# Programming_interface.net
KiCad netlist of a schematic drawn in Altium Designer
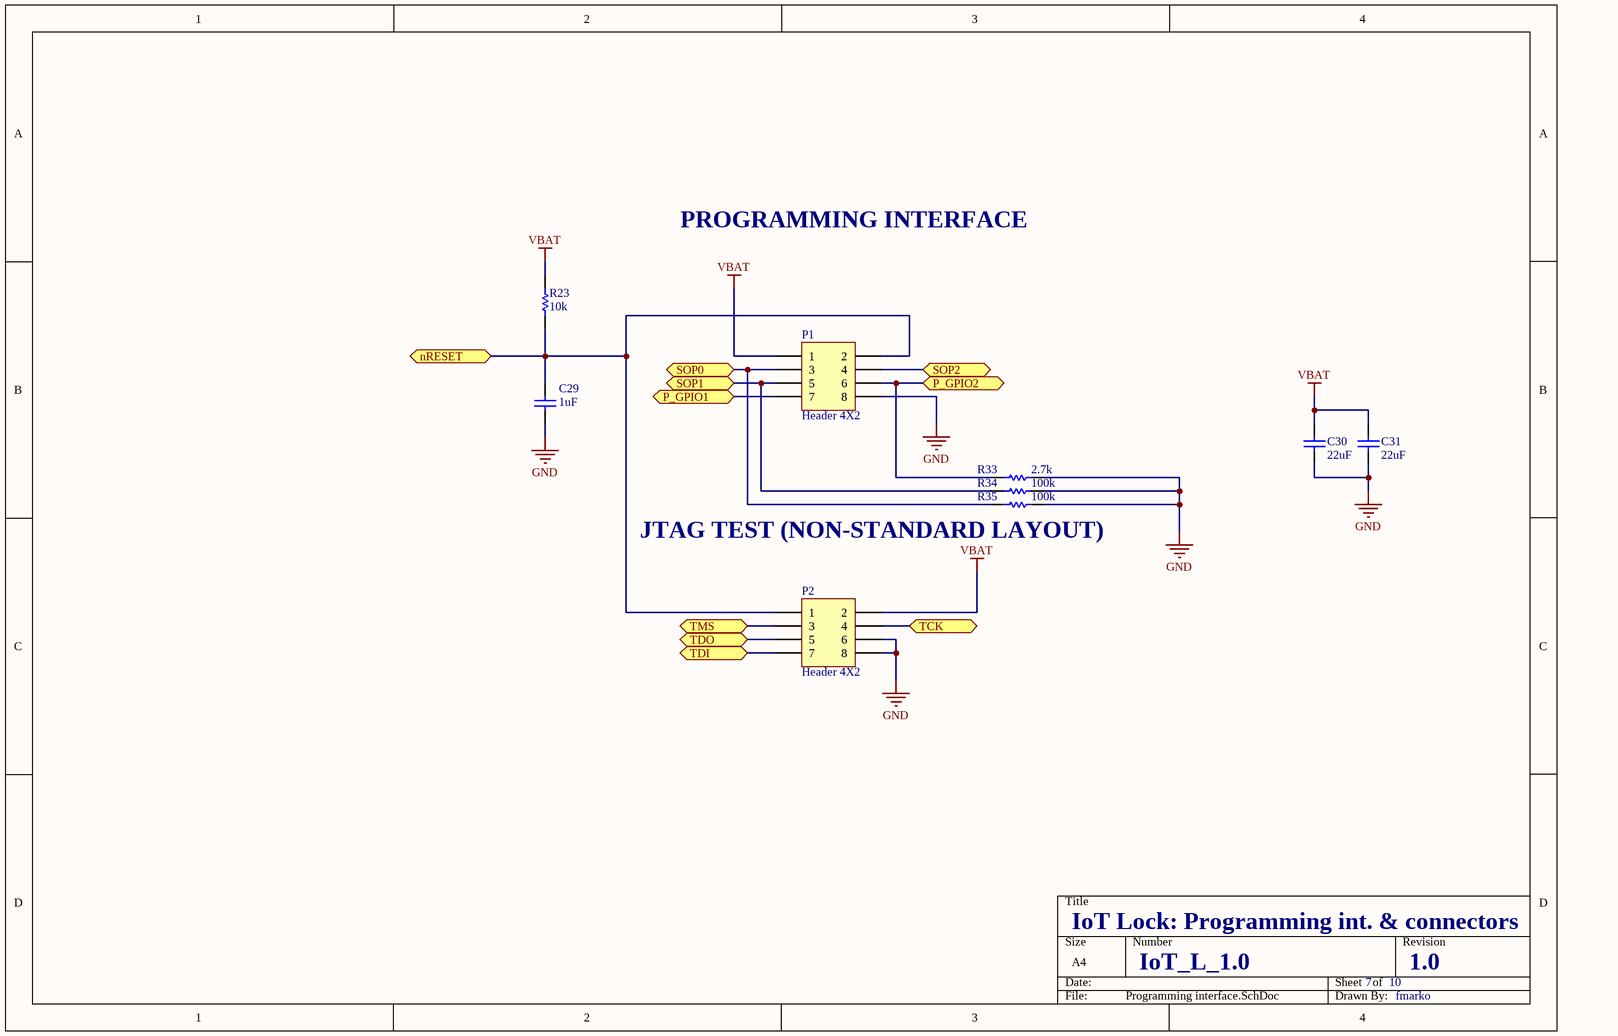
[diagram p0: Programming interface.SchDoc]

(export (version "E")
  (design (tool "Eeschema 10.0.6"))
  (components
    (comp (ref "C29")
      (value "1uF")
      (footprint "0402")
      (description "Capacitor")
      (fields (field (name "Comment") "GRM1555C1HR50BA01D") (field (name "PUBLISHER") "Altium Limited"))
      (libsource (lib "Miscellaneous Devices") (part "Cap"))
    )
    (comp (ref "C30")
      (value "22uF")
      (footprint "1608[0603]")
      (description "Capacitor")
      (fields (field (name "Comment") "GRM1555C1HR50BA01D") (field (name "PUBLISHER") "Altium Limited"))
      (libsource (lib "Miscellaneous Devices") (part "Cap"))
    )
    (comp (ref "C31")
      (value "22uF")
      (footprint "1608[0603]")
      (description "Capacitor")
      (fields (field (name "Comment") "GRM1555C1HR50BA01D") (field (name "PUBLISHER") "Altium Limited"))
      (libsource (lib "Miscellaneous Devices") (part "Cap"))
    )
    (comp (ref "P1")
      (value "Header 4X2")
      (footprint "HDR2X4")
      (description "Header, 4-Pin, Dual row")
      (fields (field (name "PUBLISHER") "Altium Limited"))
      (libsource (lib "Miscellaneous Connectors") (part "Header 4X2"))
    )
    (comp (ref "P2")
      (value "Header 4X2")
      (footprint "HDR2X4")
      (description "Header, 4-Pin, Dual row")
      (fields (field (name "PUBLISHER") "Altium Limited"))
      (libsource (lib "Miscellaneous Connectors") (part "Header 4X2"))
    )
    (comp (ref "R23")
      (value "10k")
      (footprint "0402")
      (description "Semiconductor Resistor")
      (fields (field (name "Comment") "Res Semi") (field (name "PUBLISHER") "Altium Limited"))
      (libsource (lib "Miscellaneous Devices") (part "Res Semi"))
    )
    (comp (ref "R33")
      (value "2.7k")
      (footprint "0402")
      (description "Semiconductor Resistor")
      (fields (field (name "Comment") "Res Semi") (field (name "PUBLISHER") "Altium Limited"))
      (libsource (lib "Miscellaneous Devices") (part "Res Semi"))
    )
    (comp (ref "R34")
      (value "100k")
      (footprint "0402")
      (description "Semiconductor Resistor")
      (fields (field (name "Comment") "Res Semi") (field (name "PUBLISHER") "Altium Limited"))
      (libsource (lib "Miscellaneous Devices") (part "Res Semi"))
    )
    (comp (ref "R35")
      (value "100k")
      (footprint "0402")
      (description "Semiconductor Resistor")
      (fields (field (name "Comment") "Res Semi") (field (name "PUBLISHER") "Altium Limited"))
      (libsource (lib "Miscellaneous Devices") (part "Res Semi"))
    )
  )
  (nets
    (net (code "1") (name "/P_GPIO1") (class "Default")
      (node (ref "P1") (pin "7") (pinfunction "7_7") (pintype "passive"))
    )
    (net (code "2") (name "/P_GPIO2") (class "Default")
      (node (ref "P1") (pin "6") (pinfunction "6_6") (pintype "passive"))
      (node (ref "R33") (pin "2") (pinfunction "2_2") (pintype "passive"))
    )
    (net (code "3") (name "/SOP0") (class "Default")
      (node (ref "P1") (pin "3") (pinfunction "3_3") (pintype "passive"))
      (node (ref "R35") (pin "2") (pinfunction "2_2") (pintype "passive"))
    )
    (net (code "4") (name "/SOP1") (class "Default")
      (node (ref "P1") (pin "5") (pinfunction "5_5") (pintype "passive"))
      (node (ref "R34") (pin "2") (pinfunction "2_2") (pintype "passive"))
    )
    (net (code "5") (name "/SOP2") (class "Default")
      (node (ref "P1") (pin "4") (pinfunction "4_4") (pintype "passive"))
    )
    (net (code "6") (name "/TCK") (class "Default")
      (node (ref "P2") (pin "4") (pinfunction "4_4") (pintype "passive"))
    )
    (net (code "7") (name "/TDI") (class "Default")
      (node (ref "P2") (pin "7") (pinfunction "7_7") (pintype "passive"))
    )
    (net (code "8") (name "/TDO") (class "Default")
      (node (ref "P2") (pin "5") (pinfunction "5_5") (pintype "passive"))
    )
    (net (code "9") (name "/TMS") (class "Default")
      (node (ref "P2") (pin "3") (pinfunction "3_3") (pintype "passive"))
    )
    (net (code "10") (name "/nRESET") (class "Default")
      (node (ref "C29") (pin "2") (pinfunction "2_2") (pintype "passive"))
      (node (ref "P1") (pin "2") (pinfunction "2_2") (pintype "passive"))
      (node (ref "P2") (pin "1") (pinfunction "1_1") (pintype "passive"))
      (node (ref "R23") (pin "1") (pinfunction "1_1") (pintype "passive"))
    )
    (net (code "11") (name "GND") (class "Default")
      (node (ref "C29") (pin "1") (pinfunction "1_1") (pintype "passive"))
      (node (ref "C30") (pin "1") (pinfunction "1_1") (pintype "passive"))
      (node (ref "C31") (pin "1") (pinfunction "1_1") (pintype "passive"))
      (node (ref "P1") (pin "8") (pinfunction "8_8") (pintype "passive"))
      (node (ref "P2") (pin "6") (pinfunction "6_6") (pintype "passive"))
      (node (ref "P2") (pin "8") (pinfunction "8_8") (pintype "passive"))
      (node (ref "R33") (pin "1") (pinfunction "1_1") (pintype "passive"))
      (node (ref "R34") (pin "1") (pinfunction "1_1") (pintype "passive"))
      (node (ref "R35") (pin "1") (pinfunction "1_1") (pintype "passive"))
    )
    (net (code "12") (name "VBAT") (class "Default")
      (node (ref "C30") (pin "2") (pinfunction "2_2") (pintype "passive"))
      (node (ref "C31") (pin "2") (pinfunction "2_2") (pintype "passive"))
      (node (ref "P1") (pin "1") (pinfunction "1_1") (pintype "passive"))
      (node (ref "P2") (pin "2") (pinfunction "2_2") (pintype "passive"))
      (node (ref "R23") (pin "2") (pinfunction "2_2") (pintype "passive"))
    )
  )
)
